# beeper.net
KiCad netlist of a schematic drawn in EAGLE
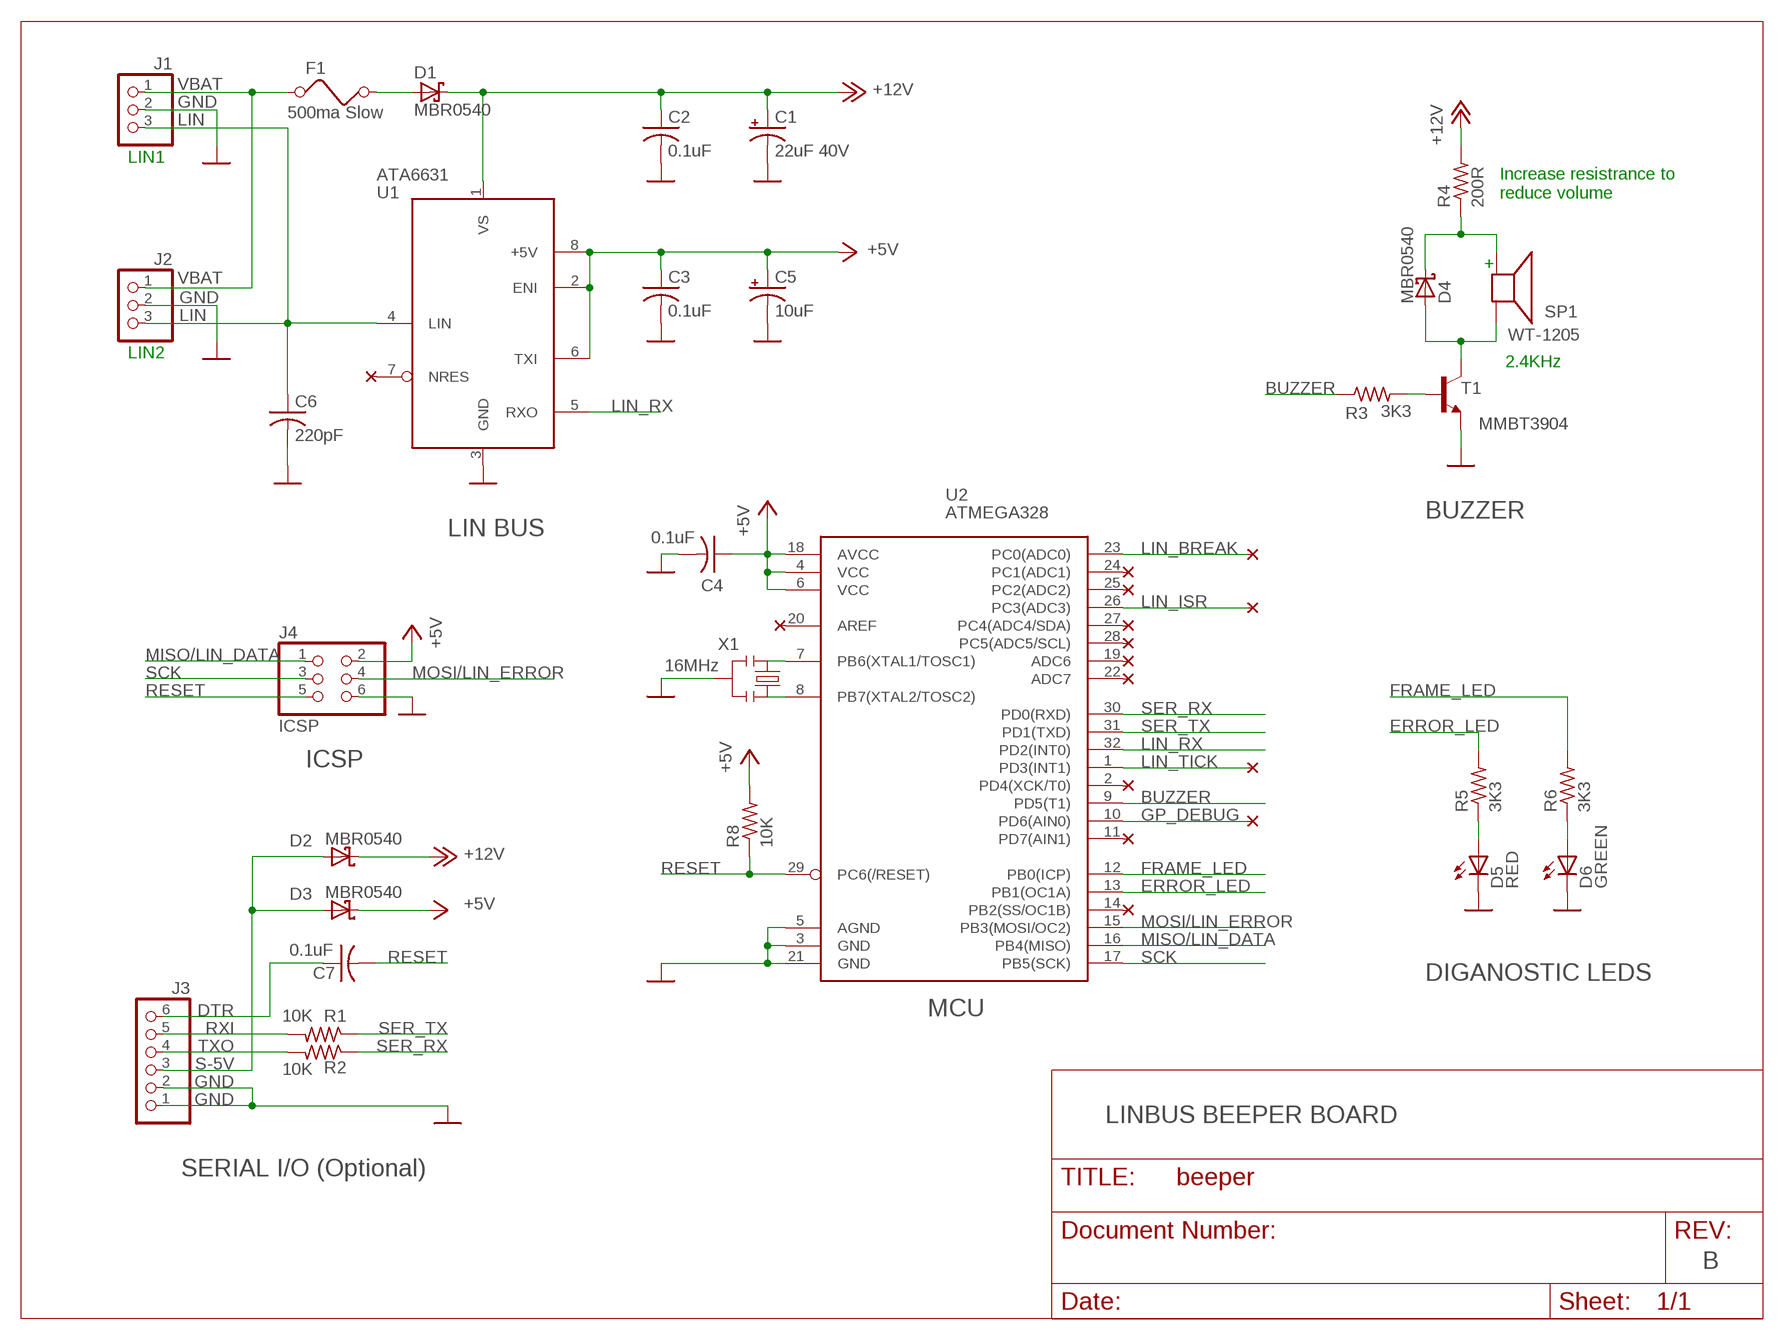
[diagram p0: schematic, sheet 1]

(export (version "E")
  (design (tool "Eeschema 10.0.6"))
  (components
    (comp (ref "C1")
      (value "22uF 40V")
      (footprint "eagle-import:UD-6,3X5,8_NICHICON")
      (libsource (lib "eagle-import") (part "CPOL-USUD-6,3X5,8"))
    )
    (comp (ref "C2")
      (value "0.1uF")
      (footprint "eagle-import:C0805")
      (libsource (lib "eagle-import") (part "C-USC0805"))
    )
    (comp (ref "C3")
      (value "0.1uF")
      (footprint "eagle-import:C0805")
      (libsource (lib "eagle-import") (part "C-USC0805"))
    )
    (comp (ref "C4")
      (value "0.1uF")
      (footprint "eagle-import:C0805")
      (libsource (lib "eagle-import") (part "C-USC0805"))
    )
    (comp (ref "C5")
      (value "10uF")
      (footprint "eagle-import:A_3216-18R")
      (libsource (lib "eagle-import") (part "CPOL-USA/3216-18R"))
    )
    (comp (ref "C6")
      (value "220pF")
      (footprint "eagle-import:C0805")
      (libsource (lib "eagle-import") (part "C-USC0805"))
    )
    (comp (ref "C7")
      (value "0.1uF")
      (footprint "eagle-import:C0805")
      (libsource (lib "eagle-import") (part "C-USC0805"))
    )
    (comp (ref "D1")
      (value "MBR0540")
      (footprint "eagle-import:SOD123FL")
      (libsource (lib "eagle-import") (part "SMF5.0AT1"))
    )
    (comp (ref "D2")
      (value "MBR0540")
      (footprint "eagle-import:SOD123FL")
      (libsource (lib "eagle-import") (part "SMF5.0AT1"))
    )
    (comp (ref "D3")
      (value "MBR0540")
      (footprint "eagle-import:SOD123FL")
      (libsource (lib "eagle-import") (part "SMF5.0AT1"))
    )
    (comp (ref "D4")
      (value "MBR0540")
      (footprint "eagle-import:SOD123FL")
      (libsource (lib "eagle-import") (part "SMF5.0AT1"))
    )
    (comp (ref "D5")
      (value "RED")
      (footprint "eagle-import:1206-LED")
      (libsource (lib "eagle-import") (part "LED"))
    )
    (comp (ref "D6")
      (value "GREEN")
      (footprint "eagle-import:1206-LED")
      (libsource (lib "eagle-import") (part "LED"))
    )
    (comp (ref "F1")
      (value "500ma Slow")
      (footprint "eagle-import:1206")
      (libsource (lib "eagle-import") (part "FUSE"))
    )
    (comp (ref "J1")
      (value "PINHD-1X3")
      (footprint "eagle-import:1X03")
      (libsource (lib "eagle-import") (part "PINHD-1X3"))
    )
    (comp (ref "J2")
      (value "PINHD-1X3")
      (footprint "eagle-import:1X03")
      (libsource (lib "eagle-import") (part "PINHD-1X3"))
    )
    (comp (ref "J3")
      (value "PINHD-1X6")
      (footprint "eagle-import:1X06")
      (libsource (lib "eagle-import") (part "PINHD-1X6"))
    )
    (comp (ref "J4")
      (value "ICSP")
      (footprint "eagle-import:2X03")
      (libsource (lib "eagle-import") (part "PINHD-2X3"))
    )
    (comp (ref "R1")
      (value "10K")
      (footprint "eagle-import:R0805")
      (libsource (lib "eagle-import") (part "R-US_R0805"))
    )
    (comp (ref "R2")
      (value "10K")
      (footprint "eagle-import:R0805")
      (libsource (lib "eagle-import") (part "R-US_R0805"))
    )
    (comp (ref "R3")
      (value "3K3")
      (footprint "eagle-import:R0805")
      (libsource (lib "eagle-import") (part "R-US_R0805"))
    )
    (comp (ref "R4")
      (value "200R")
      (footprint "eagle-import:R0805")
      (libsource (lib "eagle-import") (part "R-US_R0805"))
    )
    (comp (ref "R5")
      (value "3K3")
      (footprint "eagle-import:R0805")
      (libsource (lib "eagle-import") (part "R-US_R0805"))
    )
    (comp (ref "R6")
      (value "3K3")
      (footprint "eagle-import:R0805")
      (libsource (lib "eagle-import") (part "R-US_R0805"))
    )
    (comp (ref "R8")
      (value "10K")
      (footprint "eagle-import:R0805")
      (libsource (lib "eagle-import") (part "R-US_R0805"))
    )
    (comp (ref "SP1")
      (value "WT-1205")
      (footprint "eagle-import:AL60P")
      (libsource (lib "eagle-import") (part "AL60P"))
    )
    (comp (ref "T1")
      (value "MMBT3904")
      (footprint "eagle-import:SOT23-BEC")
      (libsource (lib "eagle-import") (part "-NPN-SOT23-BECMMBT3904LT1"))
    )
    (comp (ref "U1")
      (value "ATA6631")
      (footprint "eagle-import:SO-08")
      (libsource (lib "eagle-import") (part "ATA6631"))
    )
    (comp (ref "U2")
      (value "ATMEGA328")
      (footprint "eagle-import:TQFP32-08")
      (libsource (lib "eagle-import") (part "ATMEGA328"))
    )
    (comp (ref "X1")
      (value "16MHz")
      (footprint "eagle-import:RESONATOR-SMD")
      (libsource (lib "eagle-import") (part "RESONATORSMD"))
    )
  )
  (nets
    (net (code "1") (name "+5V") (class "Default")
      (node (ref "C3") (pin "1") (pinfunction "1_1") (pintype "passive"))
      (node (ref "C4") (pin "1") (pinfunction "1_1") (pintype "passive"))
      (node (ref "C5") (pin "+") (pinfunction "+_+") (pintype "passive"))
      (node (ref "D3") (pin "C") (pinfunction "C_C") (pintype "passive"))
      (node (ref "J4") (pin "2") (pinfunction "2_2") (pintype "passive"))
      (node (ref "R8") (pin "2") (pinfunction "2_2") (pintype "passive"))
      (node (ref "U1") (pin "2") (pinfunction "ENI_2") (pintype "input"))
      (node (ref "U1") (pin "6") (pinfunction "TXI_6") (pintype "input"))
      (node (ref "U1") (pin "8") (pinfunction "+5V_8") (pintype "power_in"))
      (node (ref "U2") (pin "18") (pinfunction "AVCC_18") (pintype "power_in"))
      (node (ref "U2") (pin "4") (pinfunction "VCC_4") (pintype "power_in"))
      (node (ref "U2") (pin "6") (pinfunction "VCC_6") (pintype "power_in"))
    )
    (net (code "2") (name "+12V") (class "Default")
      (node (ref "C1") (pin "+") (pinfunction "+_+") (pintype "passive"))
      (node (ref "C2") (pin "1") (pinfunction "1_1") (pintype "passive"))
      (node (ref "D1") (pin "C") (pinfunction "C_C") (pintype "passive"))
      (node (ref "D2") (pin "C") (pinfunction "C_C") (pintype "passive"))
      (node (ref "R4") (pin "2") (pinfunction "2_2") (pintype "passive"))
      (node (ref "U1") (pin "1") (pinfunction "VS_1") (pintype "power_in"))
    )
    (net (code "3") (name "/AREF") (class "Default")
      (node (ref "U2") (pin "20") (pinfunction "AREF_20") (pintype "power_in"))
    )
    (net (code "4") (name "/BUZZER") (class "Default")
      (node (ref "R3") (pin "1") (pinfunction "1_1") (pintype "passive"))
      (node (ref "U2") (pin "9") (pinfunction "PD5(T1)_9") (pintype "bidirectional"))
    )
    (net (code "5") (name "/DTR") (class "Default")
      (node (ref "C7") (pin "1") (pinfunction "1_1") (pintype "passive"))
      (node (ref "J3") (pin "6") (pinfunction "6_6") (pintype "passive"))
    )
    (net (code "6") (name "/ERROR_LED") (class "Default")
      (node (ref "R5") (pin "2") (pinfunction "2_2") (pintype "passive"))
      (node (ref "U2") (pin "13") (pinfunction "PB1(OC1A)_13") (pintype "bidirectional"))
    )
    (net (code "7") (name "/FRAME_LED") (class "Default")
      (node (ref "R6") (pin "2") (pinfunction "2_2") (pintype "passive"))
      (node (ref "U2") (pin "12") (pinfunction "PB0(ICP)_12") (pintype "bidirectional"))
    )
    (net (code "8") (name "/GP_DEBUG") (class "Default")
      (node (ref "U2") (pin "10") (pinfunction "PD6(AIN0)_10") (pintype "bidirectional"))
    )
    (net (code "9") (name "/LIN") (class "Default")
      (node (ref "C6") (pin "1") (pinfunction "1_1") (pintype "passive"))
      (node (ref "J1") (pin "3") (pinfunction "3_3") (pintype "passive"))
      (node (ref "J2") (pin "3") (pinfunction "3_3") (pintype "passive"))
      (node (ref "U1") (pin "4") (pinfunction "LIN_4") (pintype "bidirectional"))
    )
    (net (code "10") (name "/LIN_BREAK") (class "Default")
      (node (ref "U2") (pin "23") (pinfunction "PC0(ADC0)_23") (pintype "bidirectional"))
    )
    (net (code "11") (name "/LIN_ISR") (class "Default")
      (node (ref "U2") (pin "26") (pinfunction "PC3(ADC3)_26") (pintype "bidirectional"))
    )
    (net (code "12") (name "/LIN_RX") (class "Default")
      (node (ref "U1") (pin "5") (pinfunction "RXO_5") (pintype "output"))
      (node (ref "U2") (pin "32") (pinfunction "PD2(INT0)_32") (pintype "bidirectional"))
    )
    (net (code "13") (name "/LIN_TICK") (class "Default")
      (node (ref "U2") (pin "1") (pinfunction "PD3(INT1)_1") (pintype "bidirectional"))
    )
    (net (code "14") (name "/MISO{slash}LIN_DATA") (class "Default")
      (node (ref "J4") (pin "1") (pinfunction "1_1") (pintype "passive"))
      (node (ref "U2") (pin "16") (pinfunction "PB4(MISO)_16") (pintype "bidirectional"))
    )
    (net (code "15") (name "/MOSI{slash}LIN_ERROR") (class "Default")
      (node (ref "J4") (pin "4") (pinfunction "4_4") (pintype "passive"))
      (node (ref "U2") (pin "15") (pinfunction "PB3(MOSI/OC2)_15") (pintype "bidirectional"))
    )
    (net (code "16") (name "/RESET") (class "Default")
      (node (ref "C7") (pin "2") (pinfunction "2_2") (pintype "passive"))
      (node (ref "J4") (pin "5") (pinfunction "5_5") (pintype "passive"))
      (node (ref "R8") (pin "1") (pinfunction "1_1") (pintype "passive"))
      (node (ref "U2") (pin "29") (pinfunction "PC6(/RESET)_29") (pintype "bidirectional"))
    )
    (net (code "17") (name "/RXI") (class "Default")
      (node (ref "J3") (pin "5") (pinfunction "5_5") (pintype "passive"))
      (node (ref "R1") (pin "2") (pinfunction "2_2") (pintype "passive"))
    )
    (net (code "18") (name "/S-5V") (class "Default")
      (node (ref "D2") (pin "A") (pinfunction "A_A") (pintype "passive"))
      (node (ref "D3") (pin "A") (pinfunction "A_A") (pintype "passive"))
      (node (ref "J3") (pin "3") (pinfunction "3_3") (pintype "passive"))
    )
    (net (code "19") (name "/SCK") (class "Default")
      (node (ref "J4") (pin "3") (pinfunction "3_3") (pintype "passive"))
      (node (ref "U2") (pin "17") (pinfunction "PB5(SCK)_17") (pintype "bidirectional"))
    )
    (net (code "20") (name "/SER_RX") (class "Default")
      (node (ref "R2") (pin "1") (pinfunction "1_1") (pintype "passive"))
      (node (ref "U2") (pin "30") (pinfunction "PD0(RXD)_30") (pintype "bidirectional"))
    )
    (net (code "21") (name "/SER_TX") (class "Default")
      (node (ref "R1") (pin "1") (pinfunction "1_1") (pintype "passive"))
      (node (ref "U2") (pin "31") (pinfunction "PD1(TXD)_31") (pintype "bidirectional"))
    )
    (net (code "22") (name "/TXO") (class "Default")
      (node (ref "J3") (pin "4") (pinfunction "4_4") (pintype "passive"))
      (node (ref "R2") (pin "2") (pinfunction "2_2") (pintype "passive"))
    )
    (net (code "23") (name "/VBAT") (class "Default")
      (node (ref "F1") (pin "1") (pinfunction "1_1") (pintype "passive"))
      (node (ref "J1") (pin "1") (pinfunction "1_1") (pintype "passive"))
      (node (ref "J2") (pin "1") (pinfunction "1_1") (pintype "passive"))
    )
    (net (code "24") (name "GND") (class "Default")
      (node (ref "C1") (pin "-") (pinfunction "-_-") (pintype "passive"))
      (node (ref "C2") (pin "2") (pinfunction "2_2") (pintype "passive"))
      (node (ref "C3") (pin "2") (pinfunction "2_2") (pintype "passive"))
      (node (ref "C4") (pin "2") (pinfunction "2_2") (pintype "passive"))
      (node (ref "C5") (pin "-") (pinfunction "-_-") (pintype "passive"))
      (node (ref "C6") (pin "2") (pinfunction "2_2") (pintype "passive"))
      (node (ref "D5") (pin "C") (pinfunction "C_C") (pintype "passive"))
      (node (ref "D6") (pin "C") (pinfunction "C_C") (pintype "passive"))
      (node (ref "J1") (pin "2") (pinfunction "2_2") (pintype "passive"))
      (node (ref "J2") (pin "2") (pinfunction "2_2") (pintype "passive"))
      (node (ref "J3") (pin "1") (pinfunction "1_1") (pintype "passive"))
      (node (ref "J3") (pin "2") (pinfunction "2_2") (pintype "passive"))
      (node (ref "J4") (pin "6") (pinfunction "6_6") (pintype "passive"))
      (node (ref "T1") (pin "E") (pinfunction "E_E") (pintype "passive"))
      (node (ref "U1") (pin "3") (pinfunction "GND_3") (pintype "power_in"))
      (node (ref "U2") (pin "21") (pinfunction "GND_21") (pintype "power_in"))
      (node (ref "U2") (pin "3") (pinfunction "GND_3") (pintype "power_in"))
      (node (ref "U2") (pin "5") (pinfunction "AGND_5") (pintype "power_in"))
      (node (ref "X1") (pin "2") (pinfunction "2_2") (pintype "passive"))
    )
    (net (code "25") (name "Net-(D1-PadA)") (class "Default")
      (node (ref "D1") (pin "A") (pinfunction "A_A") (pintype "passive"))
      (node (ref "F1") (pin "2") (pinfunction "2_2") (pintype "passive"))
    )
    (net (code "26") (name "Net-(D4-PadA)") (class "Default")
      (node (ref "D4") (pin "A") (pinfunction "A_A") (pintype "passive"))
      (node (ref "SP1") (pin "2") (pinfunction "2_2") (pintype "passive"))
      (node (ref "T1") (pin "C") (pinfunction "C_C") (pintype "passive"))
    )
    (net (code "27") (name "Net-(D4-PadC)") (class "Default")
      (node (ref "D4") (pin "C") (pinfunction "C_C") (pintype "passive"))
      (node (ref "R4") (pin "1") (pinfunction "1_1") (pintype "passive"))
      (node (ref "SP1") (pin "1") (pinfunction "1_1") (pintype "passive"))
    )
    (net (code "28") (name "Net-(D5-PadA)") (class "Default")
      (node (ref "D5") (pin "A") (pinfunction "A_A") (pintype "passive"))
      (node (ref "R5") (pin "1") (pinfunction "1_1") (pintype "passive"))
    )
    (net (code "29") (name "Net-(D6-PadA)") (class "Default")
      (node (ref "D6") (pin "A") (pinfunction "A_A") (pintype "passive"))
      (node (ref "R6") (pin "1") (pinfunction "1_1") (pintype "passive"))
    )
    (net (code "30") (name "Net-(R3-Pad2)") (class "Default")
      (node (ref "R3") (pin "2") (pinfunction "2_2") (pintype "passive"))
      (node (ref "T1") (pin "B") (pinfunction "B_B") (pintype "passive"))
    )
    (net (code "31") (name "Net-(U2-PB6(XTAL1{slash}TOSC1))") (class "Default")
      (node (ref "U2") (pin "7") (pinfunction "PB6(XTAL1/TOSC1)_7") (pintype "bidirectional"))
      (node (ref "X1") (pin "3") (pinfunction "3_3") (pintype "passive"))
    )
    (net (code "32") (name "Net-(U2-PB7(XTAL2{slash}TOSC2))") (class "Default")
      (node (ref "U2") (pin "8") (pinfunction "PB7(XTAL2/TOSC2)_8") (pintype "bidirectional"))
      (node (ref "X1") (pin "1") (pinfunction "1_1") (pintype "passive"))
    )
    (net (code "33") (name "unconnected-(U1-NRES-Pad7)") (class "Default")
      (node (ref "U1") (pin "7") (pinfunction "NRES_7") (pintype "output"))
    )
    (net (code "34") (name "unconnected-(U2-ADC6-Pad19)") (class "Default")
      (node (ref "U2") (pin "19") (pinfunction "ADC6_19") (pintype "bidirectional"))
    )
    (net (code "35") (name "unconnected-(U2-ADC7-Pad22)") (class "Default")
      (node (ref "U2") (pin "22") (pinfunction "ADC7_22") (pintype "bidirectional"))
    )
    (net (code "36") (name "unconnected-(U2-PB2(SS{slash}OC1B)-Pad14)") (class "Default")
      (node (ref "U2") (pin "14") (pinfunction "PB2(SS/OC1B)_14") (pintype "bidirectional"))
    )
    (net (code "37") (name "unconnected-(U2-PC1(ADC1)-Pad24)") (class "Default")
      (node (ref "U2") (pin "24") (pinfunction "PC1(ADC1)_24") (pintype "bidirectional"))
    )
    (net (code "38") (name "unconnected-(U2-PC2(ADC2)-Pad25)") (class "Default")
      (node (ref "U2") (pin "25") (pinfunction "PC2(ADC2)_25") (pintype "bidirectional"))
    )
    (net (code "39") (name "unconnected-(U2-PC4(ADC4{slash}SDA)-Pad27)") (class "Default")
      (node (ref "U2") (pin "27") (pinfunction "PC4(ADC4/SDA)_27") (pintype "bidirectional"))
    )
    (net (code "40") (name "unconnected-(U2-PC5(ADC5{slash}SCL)-Pad28)") (class "Default")
      (node (ref "U2") (pin "28") (pinfunction "PC5(ADC5/SCL)_28") (pintype "bidirectional"))
    )
    (net (code "41") (name "unconnected-(U2-PD4(XCK{slash}T0)-Pad2)") (class "Default")
      (node (ref "U2") (pin "2") (pinfunction "PD4(XCK/T0)_2") (pintype "bidirectional"))
    )
    (net (code "42") (name "unconnected-(U2-PD7(AIN1)-Pad11)") (class "Default")
      (node (ref "U2") (pin "11") (pinfunction "PD7(AIN1)_11") (pintype "bidirectional"))
    )
  )
)
